# Lumiboard_-_sensor_board_rev_A.net
KiCad netlist of a schematic drawn in EAGLE
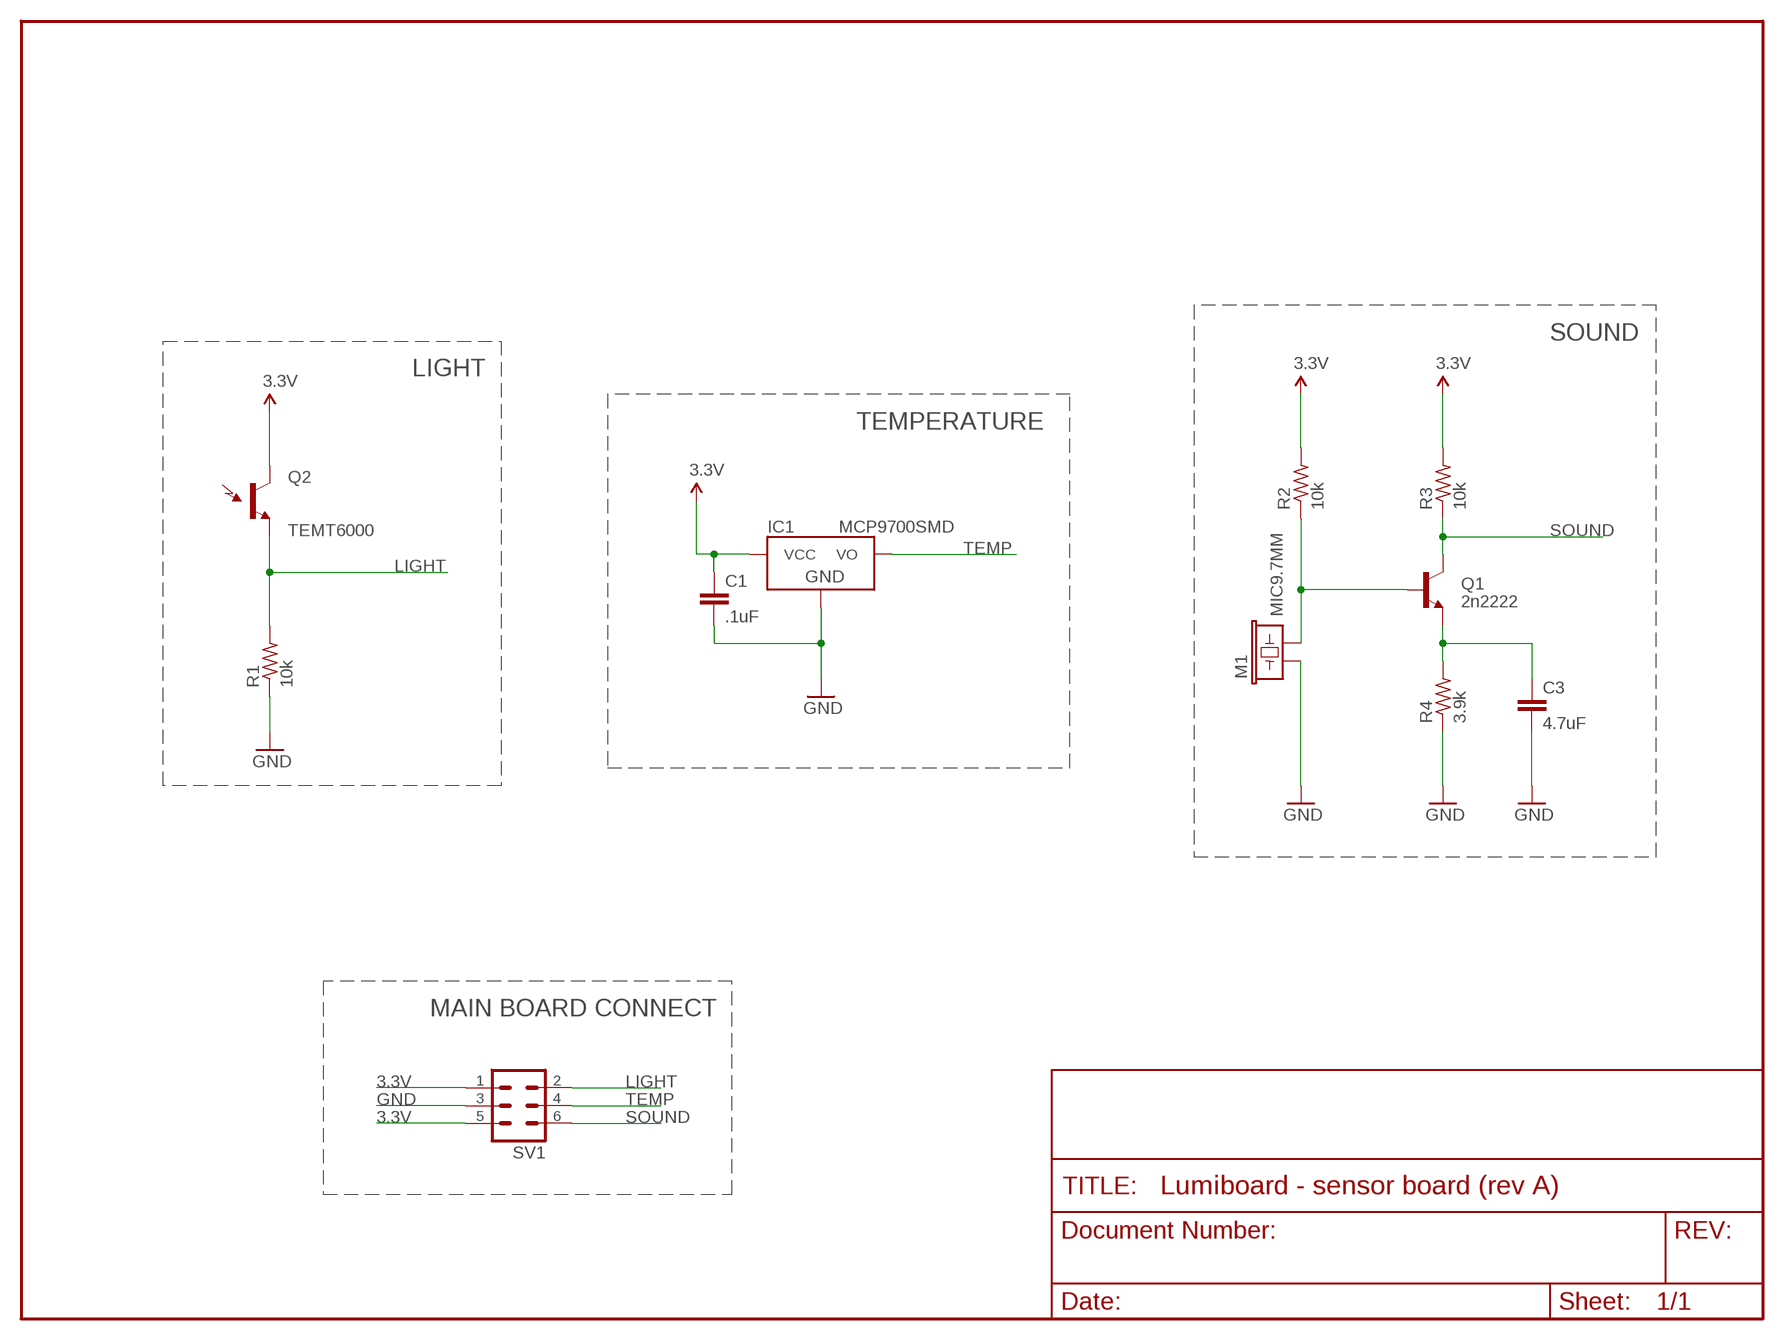
[diagram p0: schematic, sheet 1]

(export (version "E")
  (design (tool "Eeschema 10.0.6"))
  (components
    (comp (ref "C1")
      (value ".1uF")
      (footprint "eagle-import:0805")
      (libsource (lib "eagle-import") (part "CAP0805"))
    )
    (comp (ref "C3")
      (value "4.7uF")
      (footprint "eagle-import:0805")
      (libsource (lib "eagle-import") (part "CAP0805"))
    )
    (comp (ref "IC1")
      (value "MCP9700SMD")
      (footprint "eagle-import:SOT23-3")
      (libsource (lib "eagle-import") (part "MCP9700SMD"))
    )
    (comp (ref "M1")
      (value "MIC9.7MM")
      (footprint "eagle-import:MIC-9.7MM")
      (libsource (lib "eagle-import") (part "MIC9.7MM"))
    )
    (comp (ref "Q1")
      (value "2n2222")
      (footprint "eagle-import:SOT23-3")
      (libsource (lib "eagle-import") (part "TRANSISTOR_NPNSOT23-3"))
    )
    (comp (ref "Q2")
      (value "TEMT6000")
      (footprint "eagle-import:TEMT6000-SEN")
      (libsource (lib "eagle-import") (part "TEMT6000"))
    )
    (comp (ref "R1")
      (value "10k")
      (footprint "eagle-import:R0805")
      (libsource (lib "eagle-import") (part "R-US_R0805"))
    )
    (comp (ref "R2")
      (value "10k")
      (footprint "eagle-import:R0805")
      (libsource (lib "eagle-import") (part "R-US_R0805"))
    )
    (comp (ref "R3")
      (value "10k")
      (footprint "eagle-import:R0805")
      (libsource (lib "eagle-import") (part "R-US_R0805"))
    )
    (comp (ref "R4")
      (value "3.9k")
      (footprint "eagle-import:R0805")
      (libsource (lib "eagle-import") (part "R-US_R0805"))
    )
    (comp (ref "SV1")
      (value "ML6")
      (footprint "eagle-import:ML6")
      (libsource (lib "eagle-import") (part "ML6"))
    )
  )
  (nets
    (net (code "1") (name "/LIGHT") (class "Default")
      (node (ref "Q2") (pin "EMITTER") (pinfunction "E1_EMITTER") (pintype "passive"))
      (node (ref "R1") (pin "2") (pinfunction "2_2") (pintype "passive"))
      (node (ref "SV1") (pin "2") (pinfunction "2_2") (pintype "passive"))
    )
    (net (code "2") (name "/SOUND") (class "Default")
      (node (ref "Q1") (pin "3") (pinfunction "C_3") (pintype "passive"))
      (node (ref "R3") (pin "1") (pinfunction "1_1") (pintype "passive"))
      (node (ref "SV1") (pin "6") (pinfunction "6_6") (pintype "passive"))
    )
    (net (code "3") (name "/TEMP") (class "Default")
      (node (ref "IC1") (pin "2") (pinfunction "VO_2") (pintype "bidirectional"))
      (node (ref "SV1") (pin "4") (pinfunction "4_4") (pintype "passive"))
    )
    (net (code "4") (name "3.3V") (class "Default")
      (node (ref "C1") (pin "1") (pinfunction "1_1") (pintype "passive"))
      (node (ref "IC1") (pin "1") (pinfunction "VCC_1") (pintype "bidirectional"))
      (node (ref "Q2") (pin "COLLECTOR") (pinfunction "C1_COLLECTOR") (pintype "passive"))
      (node (ref "R2") (pin "2") (pinfunction "2_2") (pintype "passive"))
      (node (ref "R3") (pin "2") (pinfunction "2_2") (pintype "passive"))
      (node (ref "SV1") (pin "1") (pinfunction "1_1") (pintype "passive"))
      (node (ref "SV1") (pin "5") (pinfunction "5_5") (pintype "passive"))
    )
    (net (code "5") (name "GND") (class "Default")
      (node (ref "C1") (pin "2") (pinfunction "2_2") (pintype "passive"))
      (node (ref "C3") (pin "2") (pinfunction "2_2") (pintype "passive"))
      (node (ref "IC1") (pin "3") (pinfunction "GND_3") (pintype "bidirectional"))
      (node (ref "M1") (pin "1") (pinfunction "1_1") (pintype "passive"))
      (node (ref "R1") (pin "1") (pinfunction "1_1") (pintype "passive"))
      (node (ref "R4") (pin "1") (pinfunction "1_1") (pintype "passive"))
      (node (ref "SV1") (pin "3") (pinfunction "3_3") (pintype "passive"))
    )
    (net (code "6") (name "Net-(Q1-B)") (class "Default")
      (node (ref "M1") (pin "2") (pinfunction "2_2") (pintype "passive"))
      (node (ref "Q1") (pin "1") (pinfunction "B_1") (pintype "passive"))
      (node (ref "R2") (pin "1") (pinfunction "1_1") (pintype "passive"))
    )
    (net (code "7") (name "Net-(Q1-E)") (class "Default")
      (node (ref "C3") (pin "1") (pinfunction "1_1") (pintype "passive"))
      (node (ref "Q1") (pin "2") (pinfunction "E_2") (pintype "passive"))
      (node (ref "R4") (pin "2") (pinfunction "2_2") (pintype "passive"))
    )
  )
)
